# untitled.net
KiCad netlist of a schematic drawn in EAGLE
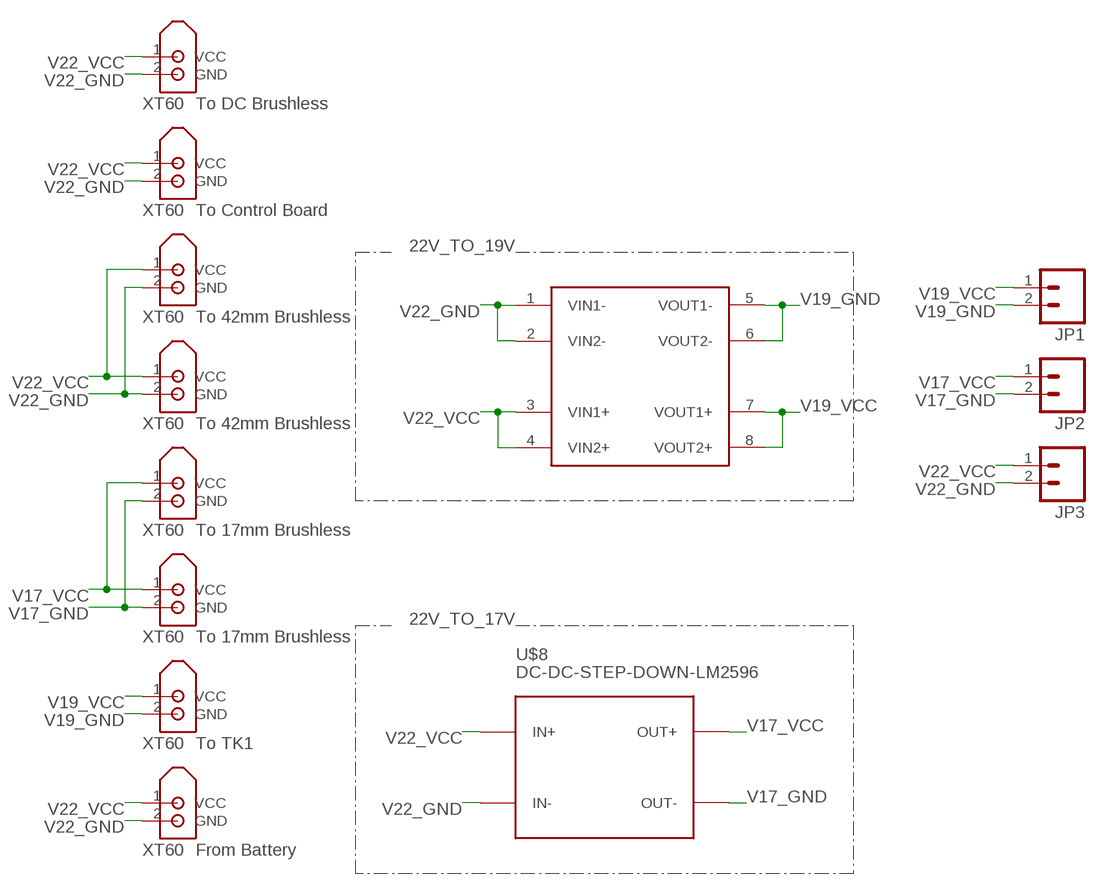
[diagram p0: schematic, sheet 1]

(export (version "E")
  (design (tool "Eeschema 10.0.6"))
  (components
    (comp (ref "JP1")
      (value "M02JST-PTH-VERT")
      (footprint "eagle-import:JST-2-PTH-VERT")
      (libsource (lib "eagle-import") (part "M02JST-PTH-VERT"))
    )
    (comp (ref "JP2")
      (value "M02JST-PTH-VERT")
      (footprint "eagle-import:JST-2-PTH-VERT")
      (libsource (lib "eagle-import") (part "M02JST-PTH-VERT"))
    )
    (comp (ref "JP3")
      (value "M02JST-PTH-VERT")
      (footprint "eagle-import:JST-2-PTH-VERT")
      (libsource (lib "eagle-import") (part "M02JST-PTH-VERT"))
    )
    (comp (ref "U$1")
      (value "XT60")
      (footprint "eagle-import:XT60")
      (libsource (lib "eagle-import") (part "XT60"))
    )
    (comp (ref "U$2")
      (value "XT60")
      (footprint "eagle-import:XT60")
      (libsource (lib "eagle-import") (part "XT60"))
    )
    (comp (ref "U$3")
      (value "XT60")
      (footprint "eagle-import:XT60")
      (libsource (lib "eagle-import") (part "XT60"))
    )
    (comp (ref "U$4")
      (value "XT60")
      (footprint "eagle-import:XT60")
      (libsource (lib "eagle-import") (part "XT60"))
    )
    (comp (ref "U$5")
      (value "XT60")
      (footprint "eagle-import:XT60")
      (libsource (lib "eagle-import") (part "XT60"))
    )
    (comp (ref "U$6")
      (value "XT60")
      (footprint "eagle-import:XT60")
      (libsource (lib "eagle-import") (part "XT60"))
    )
    (comp (ref "U$7")
      (value "MP1584")
      (footprint "eagle-import:MP1584_AMAZON")
      (libsource (lib "eagle-import") (part "MP1584"))
    )
    (comp (ref "U$8")
      (value "DC-DC-STEP-DOWN-LM2596")
      (footprint "eagle-import:DC-DC-STEP-DOWN-LM2596")
      (libsource (lib "eagle-import") (part "DC-DC-STEP-DOWN-LM2596"))
    )
    (comp (ref "U$9")
      (value "XT60")
      (footprint "eagle-import:XT60")
      (libsource (lib "eagle-import") (part "XT60"))
    )
    (comp (ref "U$10")
      (value "XT60")
      (footprint "eagle-import:XT60")
      (libsource (lib "eagle-import") (part "XT60"))
    )
  )
  (nets
    (net (code "1") (name "/V17_GND") (class "Default")
      (node (ref "JP2") (pin "2") (pinfunction "2_2") (pintype "passive"))
      (node (ref "U$3") (pin "2") (pinfunction "GND_2") (pintype "bidirectional"))
      (node (ref "U$4") (pin "2") (pinfunction "GND_2") (pintype "bidirectional"))
      (node (ref "U$8") (pin "OUT-") (pinfunction "OUT-_OUT-") (pintype "bidirectional"))
    )
    (net (code "2") (name "/V17_VCC") (class "Default")
      (node (ref "JP2") (pin "1") (pinfunction "1_1") (pintype "passive"))
      (node (ref "U$3") (pin "1") (pinfunction "VCC_1") (pintype "bidirectional"))
      (node (ref "U$4") (pin "1") (pinfunction "VCC_1") (pintype "bidirectional"))
      (node (ref "U$8") (pin "OUT+") (pinfunction "OUT+_OUT+") (pintype "bidirectional"))
    )
    (net (code "3") (name "/V19_GND") (class "Default")
      (node (ref "JP1") (pin "2") (pinfunction "2_2") (pintype "passive"))
      (node (ref "U$2") (pin "2") (pinfunction "GND_2") (pintype "bidirectional"))
      (node (ref "U$7") (pin "5") (pinfunction "VOUT1-_5") (pintype "bidirectional"))
      (node (ref "U$7") (pin "6") (pinfunction "VOUT2-_6") (pintype "bidirectional"))
    )
    (net (code "4") (name "/V19_VCC") (class "Default")
      (node (ref "JP1") (pin "1") (pinfunction "1_1") (pintype "passive"))
      (node (ref "U$2") (pin "1") (pinfunction "VCC_1") (pintype "bidirectional"))
      (node (ref "U$7") (pin "7") (pinfunction "VOUT1+_7") (pintype "bidirectional"))
      (node (ref "U$7") (pin "8") (pinfunction "VOUT2+_8") (pintype "bidirectional"))
    )
    (net (code "5") (name "/V22_GND") (class "Default")
      (node (ref "JP3") (pin "2") (pinfunction "2_2") (pintype "passive"))
      (node (ref "U$1") (pin "2") (pinfunction "GND_2") (pintype "bidirectional"))
      (node (ref "U$10") (pin "2") (pinfunction "GND_2") (pintype "bidirectional"))
      (node (ref "U$5") (pin "2") (pinfunction "GND_2") (pintype "bidirectional"))
      (node (ref "U$6") (pin "2") (pinfunction "GND_2") (pintype "bidirectional"))
      (node (ref "U$7") (pin "1") (pinfunction "VIN1-_1") (pintype "bidirectional"))
      (node (ref "U$7") (pin "2") (pinfunction "VIN2-_2") (pintype "bidirectional"))
      (node (ref "U$8") (pin "IN-") (pinfunction "IN-_IN-") (pintype "bidirectional"))
      (node (ref "U$9") (pin "2") (pinfunction "GND_2") (pintype "bidirectional"))
    )
    (net (code "6") (name "/V22_VCC") (class "Default")
      (node (ref "JP3") (pin "1") (pinfunction "1_1") (pintype "passive"))
      (node (ref "U$1") (pin "1") (pinfunction "VCC_1") (pintype "bidirectional"))
      (node (ref "U$10") (pin "1") (pinfunction "VCC_1") (pintype "bidirectional"))
      (node (ref "U$5") (pin "1") (pinfunction "VCC_1") (pintype "bidirectional"))
      (node (ref "U$6") (pin "1") (pinfunction "VCC_1") (pintype "bidirectional"))
      (node (ref "U$7") (pin "3") (pinfunction "VIN1+_3") (pintype "bidirectional"))
      (node (ref "U$7") (pin "4") (pinfunction "VIN2+_4") (pintype "bidirectional"))
      (node (ref "U$8") (pin "IN+") (pinfunction "IN+_IN+") (pintype "bidirectional"))
      (node (ref "U$9") (pin "1") (pinfunction "VCC_1") (pintype "bidirectional"))
    )
  )
)
